# input4.net
KiCad netlist of a schematic drawn in Altium Designer
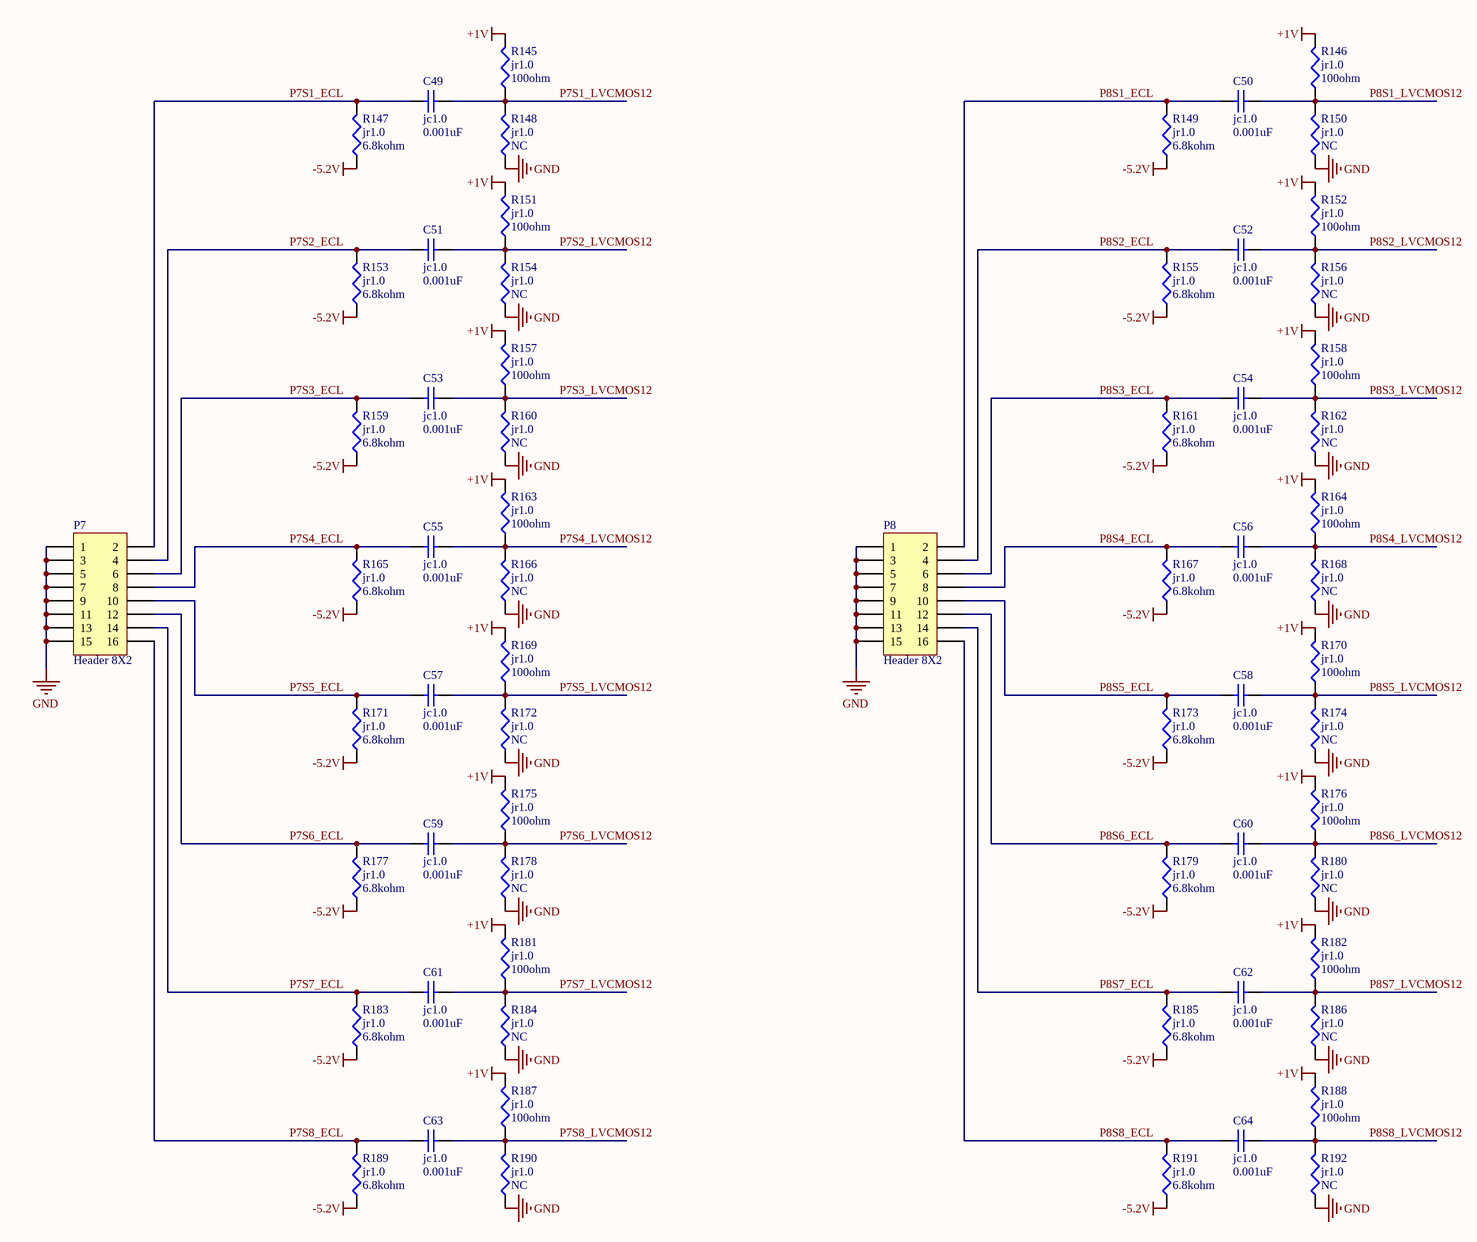
[diagram p0: input4.SchDoc]

(export (version "E")
  (design (tool "Eeschema 10.0.6"))
  (components
    (comp (ref "C49")
      (value "jc1.0")
      (footprint "0402")
      (description "Capacitor")
      (fields (field (name "ALTIUM_VALUE") "0.001uF") (field (name "PUBLISHER") "Altium Limited"))
      (libsource (lib "LIB01DXP2006SchLib") (part "Cap"))
    )
    (comp (ref "C50")
      (value "jc1.0")
      (footprint "0402")
      (description "Capacitor")
      (fields (field (name "ALTIUM_VALUE") "0.001uF") (field (name "PUBLISHER") "Altium Limited"))
      (libsource (lib "LIB01DXP2006SchLib") (part "Cap"))
    )
    (comp (ref "C51")
      (value "jc1.0")
      (footprint "0402")
      (description "Capacitor")
      (fields (field (name "ALTIUM_VALUE") "0.001uF") (field (name "PUBLISHER") "Altium Limited"))
      (libsource (lib "LIB01DXP2006SchLib") (part "Cap"))
    )
    (comp (ref "C52")
      (value "jc1.0")
      (footprint "0402")
      (description "Capacitor")
      (fields (field (name "ALTIUM_VALUE") "0.001uF") (field (name "PUBLISHER") "Altium Limited"))
      (libsource (lib "LIB01DXP2006SchLib") (part "Cap"))
    )
    (comp (ref "C53")
      (value "jc1.0")
      (footprint "0402")
      (description "Capacitor")
      (fields (field (name "ALTIUM_VALUE") "0.001uF") (field (name "PUBLISHER") "Altium Limited"))
      (libsource (lib "LIB01DXP2006SchLib") (part "Cap"))
    )
    (comp (ref "C54")
      (value "jc1.0")
      (footprint "0402")
      (description "Capacitor")
      (fields (field (name "ALTIUM_VALUE") "0.001uF") (field (name "PUBLISHER") "Altium Limited"))
      (libsource (lib "LIB01DXP2006SchLib") (part "Cap"))
    )
    (comp (ref "C55")
      (value "jc1.0")
      (footprint "0402")
      (description "Capacitor")
      (fields (field (name "ALTIUM_VALUE") "0.001uF") (field (name "PUBLISHER") "Altium Limited"))
      (libsource (lib "LIB01DXP2006SchLib") (part "Cap"))
    )
    (comp (ref "C56")
      (value "jc1.0")
      (footprint "0402")
      (description "Capacitor")
      (fields (field (name "ALTIUM_VALUE") "0.001uF") (field (name "PUBLISHER") "Altium Limited"))
      (libsource (lib "LIB01DXP2006SchLib") (part "Cap"))
    )
    (comp (ref "C57")
      (value "jc1.0")
      (footprint "0402")
      (description "Capacitor")
      (fields (field (name "ALTIUM_VALUE") "0.001uF") (field (name "PUBLISHER") "Altium Limited"))
      (libsource (lib "LIB01DXP2006SchLib") (part "Cap"))
    )
    (comp (ref "C58")
      (value "jc1.0")
      (footprint "0402")
      (description "Capacitor")
      (fields (field (name "ALTIUM_VALUE") "0.001uF") (field (name "PUBLISHER") "Altium Limited"))
      (libsource (lib "LIB01DXP2006SchLib") (part "Cap"))
    )
    (comp (ref "C59")
      (value "jc1.0")
      (footprint "0402")
      (description "Capacitor")
      (fields (field (name "ALTIUM_VALUE") "0.001uF") (field (name "PUBLISHER") "Altium Limited"))
      (libsource (lib "LIB01DXP2006SchLib") (part "Cap"))
    )
    (comp (ref "C60")
      (value "jc1.0")
      (footprint "0402")
      (description "Capacitor")
      (fields (field (name "ALTIUM_VALUE") "0.001uF") (field (name "PUBLISHER") "Altium Limited"))
      (libsource (lib "LIB01DXP2006SchLib") (part "Cap"))
    )
    (comp (ref "C61")
      (value "jc1.0")
      (footprint "0402")
      (description "Capacitor")
      (fields (field (name "ALTIUM_VALUE") "0.001uF") (field (name "PUBLISHER") "Altium Limited"))
      (libsource (lib "LIB01DXP2006SchLib") (part "Cap"))
    )
    (comp (ref "C62")
      (value "jc1.0")
      (footprint "0402")
      (description "Capacitor")
      (fields (field (name "ALTIUM_VALUE") "0.001uF") (field (name "PUBLISHER") "Altium Limited"))
      (libsource (lib "LIB01DXP2006SchLib") (part "Cap"))
    )
    (comp (ref "C63")
      (value "jc1.0")
      (footprint "0402")
      (description "Capacitor")
      (fields (field (name "ALTIUM_VALUE") "0.001uF") (field (name "PUBLISHER") "Altium Limited"))
      (libsource (lib "LIB01DXP2006SchLib") (part "Cap"))
    )
    (comp (ref "C64")
      (value "jc1.0")
      (footprint "0402")
      (description "Capacitor")
      (fields (field (name "ALTIUM_VALUE") "0.001uF") (field (name "PUBLISHER") "Altium Limited"))
      (libsource (lib "LIB01DXP2006SchLib") (part "Cap"))
    )
    (comp (ref "P7")
      (value "Header 8X2")
      (footprint "HDR2X8")
      (description "Header, 8-Pin, Dual row")
      (fields (field (name "PUBLISHER") "Altium Limited"))
      (libsource (lib "Miscellaneous Connectors") (part "Header 8X2"))
    )
    (comp (ref "P8")
      (value "Header 8X2")
      (footprint "HDR2X8")
      (description "Header, 8-Pin, Dual row")
      (fields (field (name "PUBLISHER") "Altium Limited"))
      (libsource (lib "Miscellaneous Connectors") (part "Header 8X2"))
    )
    (comp (ref "R145")
      (value "jr1.0")
      (footprint "0402")
      (description "Resistor")
      (fields (field (name "ALTIUM_VALUE") "100ohm") (field (name "PUBLISHER") "Altium Limited"))
      (libsource (lib "LIB01DXP2006SchLib") (part "Res"))
    )
    (comp (ref "R146")
      (value "jr1.0")
      (footprint "0402")
      (description "Resistor")
      (fields (field (name "ALTIUM_VALUE") "100ohm") (field (name "PUBLISHER") "Altium Limited"))
      (libsource (lib "LIB01DXP2006SchLib") (part "Res"))
    )
    (comp (ref "R147")
      (value "jr1.0")
      (footprint "0402")
      (description "Resistor")
      (fields (field (name "ALTIUM_VALUE") "6.8kohm") (field (name "PUBLISHER") "Altium Limited"))
      (libsource (lib "LIB01DXP2006SchLib") (part "Res"))
    )
    (comp (ref "R148")
      (value "jr1.0")
      (footprint "0402")
      (description "Resistor")
      (fields (field (name "ALTIUM_VALUE") "NC") (field (name "PUBLISHER") "Altium Limited"))
      (libsource (lib "LIB01DXP2006SchLib") (part "Res"))
    )
    (comp (ref "R149")
      (value "jr1.0")
      (footprint "0402")
      (description "Resistor")
      (fields (field (name "ALTIUM_VALUE") "6.8kohm") (field (name "PUBLISHER") "Altium Limited"))
      (libsource (lib "LIB01DXP2006SchLib") (part "Res"))
    )
    (comp (ref "R150")
      (value "jr1.0")
      (footprint "0402")
      (description "Resistor")
      (fields (field (name "ALTIUM_VALUE") "NC") (field (name "PUBLISHER") "Altium Limited"))
      (libsource (lib "LIB01DXP2006SchLib") (part "Res"))
    )
    (comp (ref "R151")
      (value "jr1.0")
      (footprint "0402")
      (description "Resistor")
      (fields (field (name "ALTIUM_VALUE") "100ohm") (field (name "PUBLISHER") "Altium Limited"))
      (libsource (lib "LIB01DXP2006SchLib") (part "Res"))
    )
    (comp (ref "R152")
      (value "jr1.0")
      (footprint "0402")
      (description "Resistor")
      (fields (field (name "ALTIUM_VALUE") "100ohm") (field (name "PUBLISHER") "Altium Limited"))
      (libsource (lib "LIB01DXP2006SchLib") (part "Res"))
    )
    (comp (ref "R153")
      (value "jr1.0")
      (footprint "0402")
      (description "Resistor")
      (fields (field (name "ALTIUM_VALUE") "6.8kohm") (field (name "PUBLISHER") "Altium Limited"))
      (libsource (lib "LIB01DXP2006SchLib") (part "Res"))
    )
    (comp (ref "R154")
      (value "jr1.0")
      (footprint "0402")
      (description "Resistor")
      (fields (field (name "ALTIUM_VALUE") "NC") (field (name "PUBLISHER") "Altium Limited"))
      (libsource (lib "LIB01DXP2006SchLib") (part "Res"))
    )
    (comp (ref "R155")
      (value "jr1.0")
      (footprint "0402")
      (description "Resistor")
      (fields (field (name "ALTIUM_VALUE") "6.8kohm") (field (name "PUBLISHER") "Altium Limited"))
      (libsource (lib "LIB01DXP2006SchLib") (part "Res"))
    )
    (comp (ref "R156")
      (value "jr1.0")
      (footprint "0402")
      (description "Resistor")
      (fields (field (name "ALTIUM_VALUE") "NC") (field (name "PUBLISHER") "Altium Limited"))
      (libsource (lib "LIB01DXP2006SchLib") (part "Res"))
    )
    (comp (ref "R157")
      (value "jr1.0")
      (footprint "0402")
      (description "Resistor")
      (fields (field (name "ALTIUM_VALUE") "100ohm") (field (name "PUBLISHER") "Altium Limited"))
      (libsource (lib "LIB01DXP2006SchLib") (part "Res"))
    )
    (comp (ref "R158")
      (value "jr1.0")
      (footprint "0402")
      (description "Resistor")
      (fields (field (name "ALTIUM_VALUE") "100ohm") (field (name "PUBLISHER") "Altium Limited"))
      (libsource (lib "LIB01DXP2006SchLib") (part "Res"))
    )
    (comp (ref "R159")
      (value "jr1.0")
      (footprint "0402")
      (description "Resistor")
      (fields (field (name "ALTIUM_VALUE") "6.8kohm") (field (name "PUBLISHER") "Altium Limited"))
      (libsource (lib "LIB01DXP2006SchLib") (part "Res"))
    )
    (comp (ref "R160")
      (value "jr1.0")
      (footprint "0402")
      (description "Resistor")
      (fields (field (name "ALTIUM_VALUE") "NC") (field (name "PUBLISHER") "Altium Limited"))
      (libsource (lib "LIB01DXP2006SchLib") (part "Res"))
    )
    (comp (ref "R161")
      (value "jr1.0")
      (footprint "0402")
      (description "Resistor")
      (fields (field (name "ALTIUM_VALUE") "6.8kohm") (field (name "PUBLISHER") "Altium Limited"))
      (libsource (lib "LIB01DXP2006SchLib") (part "Res"))
    )
    (comp (ref "R162")
      (value "jr1.0")
      (footprint "0402")
      (description "Resistor")
      (fields (field (name "ALTIUM_VALUE") "NC") (field (name "PUBLISHER") "Altium Limited"))
      (libsource (lib "LIB01DXP2006SchLib") (part "Res"))
    )
    (comp (ref "R163")
      (value "jr1.0")
      (footprint "0402")
      (description "Resistor")
      (fields (field (name "ALTIUM_VALUE") "100ohm") (field (name "PUBLISHER") "Altium Limited"))
      (libsource (lib "LIB01DXP2006SchLib") (part "Res"))
    )
    (comp (ref "R164")
      (value "jr1.0")
      (footprint "0402")
      (description "Resistor")
      (fields (field (name "ALTIUM_VALUE") "100ohm") (field (name "PUBLISHER") "Altium Limited"))
      (libsource (lib "LIB01DXP2006SchLib") (part "Res"))
    )
    (comp (ref "R165")
      (value "jr1.0")
      (footprint "0402")
      (description "Resistor")
      (fields (field (name "ALTIUM_VALUE") "6.8kohm") (field (name "PUBLISHER") "Altium Limited"))
      (libsource (lib "LIB01DXP2006SchLib") (part "Res"))
    )
    (comp (ref "R166")
      (value "jr1.0")
      (footprint "0402")
      (description "Resistor")
      (fields (field (name "ALTIUM_VALUE") "NC") (field (name "PUBLISHER") "Altium Limited"))
      (libsource (lib "LIB01DXP2006SchLib") (part "Res"))
    )
    (comp (ref "R167")
      (value "jr1.0")
      (footprint "0402")
      (description "Resistor")
      (fields (field (name "ALTIUM_VALUE") "6.8kohm") (field (name "PUBLISHER") "Altium Limited"))
      (libsource (lib "LIB01DXP2006SchLib") (part "Res"))
    )
    (comp (ref "R168")
      (value "jr1.0")
      (footprint "0402")
      (description "Resistor")
      (fields (field (name "ALTIUM_VALUE") "NC") (field (name "PUBLISHER") "Altium Limited"))
      (libsource (lib "LIB01DXP2006SchLib") (part "Res"))
    )
    (comp (ref "R169")
      (value "jr1.0")
      (footprint "0402")
      (description "Resistor")
      (fields (field (name "ALTIUM_VALUE") "100ohm") (field (name "PUBLISHER") "Altium Limited"))
      (libsource (lib "LIB01DXP2006SchLib") (part "Res"))
    )
    (comp (ref "R170")
      (value "jr1.0")
      (footprint "0402")
      (description "Resistor")
      (fields (field (name "ALTIUM_VALUE") "100ohm") (field (name "PUBLISHER") "Altium Limited"))
      (libsource (lib "LIB01DXP2006SchLib") (part "Res"))
    )
    (comp (ref "R171")
      (value "jr1.0")
      (footprint "0402")
      (description "Resistor")
      (fields (field (name "ALTIUM_VALUE") "6.8kohm") (field (name "PUBLISHER") "Altium Limited"))
      (libsource (lib "LIB01DXP2006SchLib") (part "Res"))
    )
    (comp (ref "R172")
      (value "jr1.0")
      (footprint "0402")
      (description "Resistor")
      (fields (field (name "ALTIUM_VALUE") "NC") (field (name "PUBLISHER") "Altium Limited"))
      (libsource (lib "LIB01DXP2006SchLib") (part "Res"))
    )
    (comp (ref "R173")
      (value "jr1.0")
      (footprint "0402")
      (description "Resistor")
      (fields (field (name "ALTIUM_VALUE") "6.8kohm") (field (name "PUBLISHER") "Altium Limited"))
      (libsource (lib "LIB01DXP2006SchLib") (part "Res"))
    )
    (comp (ref "R174")
      (value "jr1.0")
      (footprint "0402")
      (description "Resistor")
      (fields (field (name "ALTIUM_VALUE") "NC") (field (name "PUBLISHER") "Altium Limited"))
      (libsource (lib "LIB01DXP2006SchLib") (part "Res"))
    )
    (comp (ref "R175")
      (value "jr1.0")
      (footprint "0402")
      (description "Resistor")
      (fields (field (name "ALTIUM_VALUE") "100ohm") (field (name "PUBLISHER") "Altium Limited"))
      (libsource (lib "LIB01DXP2006SchLib") (part "Res"))
    )
    (comp (ref "R176")
      (value "jr1.0")
      (footprint "0402")
      (description "Resistor")
      (fields (field (name "ALTIUM_VALUE") "100ohm") (field (name "PUBLISHER") "Altium Limited"))
      (libsource (lib "LIB01DXP2006SchLib") (part "Res"))
    )
    (comp (ref "R177")
      (value "jr1.0")
      (footprint "0402")
      (description "Resistor")
      (fields (field (name "ALTIUM_VALUE") "6.8kohm") (field (name "PUBLISHER") "Altium Limited"))
      (libsource (lib "LIB01DXP2006SchLib") (part "Res"))
    )
    (comp (ref "R178")
      (value "jr1.0")
      (footprint "0402")
      (description "Resistor")
      (fields (field (name "ALTIUM_VALUE") "NC") (field (name "PUBLISHER") "Altium Limited"))
      (libsource (lib "LIB01DXP2006SchLib") (part "Res"))
    )
    (comp (ref "R179")
      (value "jr1.0")
      (footprint "0402")
      (description "Resistor")
      (fields (field (name "ALTIUM_VALUE") "6.8kohm") (field (name "PUBLISHER") "Altium Limited"))
      (libsource (lib "LIB01DXP2006SchLib") (part "Res"))
    )
    (comp (ref "R180")
      (value "jr1.0")
      (footprint "0402")
      (description "Resistor")
      (fields (field (name "ALTIUM_VALUE") "NC") (field (name "PUBLISHER") "Altium Limited"))
      (libsource (lib "LIB01DXP2006SchLib") (part "Res"))
    )
    (comp (ref "R181")
      (value "jr1.0")
      (footprint "0402")
      (description "Resistor")
      (fields (field (name "ALTIUM_VALUE") "100ohm") (field (name "PUBLISHER") "Altium Limited"))
      (libsource (lib "LIB01DXP2006SchLib") (part "Res"))
    )
    (comp (ref "R182")
      (value "jr1.0")
      (footprint "0402")
      (description "Resistor")
      (fields (field (name "ALTIUM_VALUE") "100ohm") (field (name "PUBLISHER") "Altium Limited"))
      (libsource (lib "LIB01DXP2006SchLib") (part "Res"))
    )
    (comp (ref "R183")
      (value "jr1.0")
      (footprint "0402")
      (description "Resistor")
      (fields (field (name "ALTIUM_VALUE") "6.8kohm") (field (name "PUBLISHER") "Altium Limited"))
      (libsource (lib "LIB01DXP2006SchLib") (part "Res"))
    )
    (comp (ref "R184")
      (value "jr1.0")
      (footprint "0402")
      (description "Resistor")
      (fields (field (name "ALTIUM_VALUE") "NC") (field (name "PUBLISHER") "Altium Limited"))
      (libsource (lib "LIB01DXP2006SchLib") (part "Res"))
    )
    (comp (ref "R185")
      (value "jr1.0")
      (footprint "0402")
      (description "Resistor")
      (fields (field (name "ALTIUM_VALUE") "6.8kohm") (field (name "PUBLISHER") "Altium Limited"))
      (libsource (lib "LIB01DXP2006SchLib") (part "Res"))
    )
    (comp (ref "R186")
      (value "jr1.0")
      (footprint "0402")
      (description "Resistor")
      (fields (field (name "ALTIUM_VALUE") "NC") (field (name "PUBLISHER") "Altium Limited"))
      (libsource (lib "LIB01DXP2006SchLib") (part "Res"))
    )
    (comp (ref "R187")
      (value "jr1.0")
      (footprint "0402")
      (description "Resistor")
      (fields (field (name "ALTIUM_VALUE") "100ohm") (field (name "PUBLISHER") "Altium Limited"))
      (libsource (lib "LIB01DXP2006SchLib") (part "Res"))
    )
    (comp (ref "R188")
      (value "jr1.0")
      (footprint "0402")
      (description "Resistor")
      (fields (field (name "ALTIUM_VALUE") "100ohm") (field (name "PUBLISHER") "Altium Limited"))
      (libsource (lib "LIB01DXP2006SchLib") (part "Res"))
    )
    (comp (ref "R189")
      (value "jr1.0")
      (footprint "0402")
      (description "Resistor")
      (fields (field (name "ALTIUM_VALUE") "6.8kohm") (field (name "PUBLISHER") "Altium Limited"))
      (libsource (lib "LIB01DXP2006SchLib") (part "Res"))
    )
    (comp (ref "R190")
      (value "jr1.0")
      (footprint "0402")
      (description "Resistor")
      (fields (field (name "ALTIUM_VALUE") "NC") (field (name "PUBLISHER") "Altium Limited"))
      (libsource (lib "LIB01DXP2006SchLib") (part "Res"))
    )
    (comp (ref "R191")
      (value "jr1.0")
      (footprint "0402")
      (description "Resistor")
      (fields (field (name "ALTIUM_VALUE") "6.8kohm") (field (name "PUBLISHER") "Altium Limited"))
      (libsource (lib "LIB01DXP2006SchLib") (part "Res"))
    )
    (comp (ref "R192")
      (value "jr1.0")
      (footprint "0402")
      (description "Resistor")
      (fields (field (name "ALTIUM_VALUE") "NC") (field (name "PUBLISHER") "Altium Limited"))
      (libsource (lib "LIB01DXP2006SchLib") (part "Res"))
    )
  )
  (nets
    (net (code "1") (name "+1V") (class "Default")
      (node (ref "R145") (pin "2") (pinfunction "2_2") (pintype "passive"))
      (node (ref "R146") (pin "2") (pinfunction "2_2") (pintype "passive"))
      (node (ref "R151") (pin "2") (pinfunction "2_2") (pintype "passive"))
      (node (ref "R152") (pin "2") (pinfunction "2_2") (pintype "passive"))
      (node (ref "R157") (pin "2") (pinfunction "2_2") (pintype "passive"))
      (node (ref "R158") (pin "2") (pinfunction "2_2") (pintype "passive"))
      (node (ref "R163") (pin "2") (pinfunction "2_2") (pintype "passive"))
      (node (ref "R164") (pin "2") (pinfunction "2_2") (pintype "passive"))
      (node (ref "R169") (pin "2") (pinfunction "2_2") (pintype "passive"))
      (node (ref "R170") (pin "2") (pinfunction "2_2") (pintype "passive"))
      (node (ref "R175") (pin "2") (pinfunction "2_2") (pintype "passive"))
      (node (ref "R176") (pin "2") (pinfunction "2_2") (pintype "passive"))
      (node (ref "R181") (pin "2") (pinfunction "2_2") (pintype "passive"))
      (node (ref "R182") (pin "2") (pinfunction "2_2") (pintype "passive"))
      (node (ref "R187") (pin "2") (pinfunction "2_2") (pintype "passive"))
      (node (ref "R188") (pin "2") (pinfunction "2_2") (pintype "passive"))
    )
    (net (code "2") (name "-5.2V") (class "Default")
      (node (ref "R147") (pin "1") (pinfunction "1_1") (pintype "passive"))
      (node (ref "R149") (pin "1") (pinfunction "1_1") (pintype "passive"))
      (node (ref "R153") (pin "1") (pinfunction "1_1") (pintype "passive"))
      (node (ref "R155") (pin "1") (pinfunction "1_1") (pintype "passive"))
      (node (ref "R159") (pin "1") (pinfunction "1_1") (pintype "passive"))
      (node (ref "R161") (pin "1") (pinfunction "1_1") (pintype "passive"))
      (node (ref "R165") (pin "1") (pinfunction "1_1") (pintype "passive"))
      (node (ref "R167") (pin "1") (pinfunction "1_1") (pintype "passive"))
      (node (ref "R171") (pin "1") (pinfunction "1_1") (pintype "passive"))
      (node (ref "R173") (pin "1") (pinfunction "1_1") (pintype "passive"))
      (node (ref "R177") (pin "1") (pinfunction "1_1") (pintype "passive"))
      (node (ref "R179") (pin "1") (pinfunction "1_1") (pintype "passive"))
      (node (ref "R183") (pin "1") (pinfunction "1_1") (pintype "passive"))
      (node (ref "R185") (pin "1") (pinfunction "1_1") (pintype "passive"))
      (node (ref "R189") (pin "1") (pinfunction "1_1") (pintype "passive"))
      (node (ref "R191") (pin "1") (pinfunction "1_1") (pintype "passive"))
    )
    (net (code "3") (name "/P7S1_ECL") (class "Default")
      (node (ref "C49") (pin "1") (pinfunction "1_1") (pintype "passive"))
      (node (ref "P7") (pin "2") (pinfunction "2_2") (pintype "passive"))
      (node (ref "R147") (pin "2") (pinfunction "2_2") (pintype "passive"))
    )
    (net (code "4") (name "/P7S1_LVCMOS12") (class "Default")
      (node (ref "C49") (pin "2") (pinfunction "2_2") (pintype "passive"))
      (node (ref "R145") (pin "1") (pinfunction "1_1") (pintype "passive"))
      (node (ref "R148") (pin "2") (pinfunction "2_2") (pintype "passive"))
    )
    (net (code "5") (name "/P7S2_ECL") (class "Default")
      (node (ref "C51") (pin "1") (pinfunction "1_1") (pintype "passive"))
      (node (ref "P7") (pin "4") (pinfunction "4_4") (pintype "passive"))
      (node (ref "R153") (pin "2") (pinfunction "2_2") (pintype "passive"))
    )
    (net (code "6") (name "/P7S2_LVCMOS12") (class "Default")
      (node (ref "C51") (pin "2") (pinfunction "2_2") (pintype "passive"))
      (node (ref "R151") (pin "1") (pinfunction "1_1") (pintype "passive"))
      (node (ref "R154") (pin "2") (pinfunction "2_2") (pintype "passive"))
    )
    (net (code "7") (name "/P7S3_ECL") (class "Default")
      (node (ref "C53") (pin "1") (pinfunction "1_1") (pintype "passive"))
      (node (ref "P7") (pin "6") (pinfunction "6_6") (pintype "passive"))
      (node (ref "R159") (pin "2") (pinfunction "2_2") (pintype "passive"))
    )
    (net (code "8") (name "/P7S3_LVCMOS12") (class "Default")
      (node (ref "C53") (pin "2") (pinfunction "2_2") (pintype "passive"))
      (node (ref "R157") (pin "1") (pinfunction "1_1") (pintype "passive"))
      (node (ref "R160") (pin "2") (pinfunction "2_2") (pintype "passive"))
    )
    (net (code "9") (name "/P7S4_ECL") (class "Default")
      (node (ref "C55") (pin "1") (pinfunction "1_1") (pintype "passive"))
      (node (ref "P7") (pin "8") (pinfunction "8_8") (pintype "passive"))
      (node (ref "R165") (pin "2") (pinfunction "2_2") (pintype "passive"))
    )
    (net (code "10") (name "/P7S4_LVCMOS12") (class "Default")
      (node (ref "C55") (pin "2") (pinfunction "2_2") (pintype "passive"))
      (node (ref "R163") (pin "1") (pinfunction "1_1") (pintype "passive"))
      (node (ref "R166") (pin "2") (pinfunction "2_2") (pintype "passive"))
    )
    (net (code "11") (name "/P7S5_ECL") (class "Default")
      (node (ref "C57") (pin "1") (pinfunction "1_1") (pintype "passive"))
      (node (ref "P7") (pin "10") (pinfunction "10_10") (pintype "passive"))
      (node (ref "R171") (pin "2") (pinfunction "2_2") (pintype "passive"))
    )
    (net (code "12") (name "/P7S5_LVCMOS12") (class "Default")
      (node (ref "C57") (pin "2") (pinfunction "2_2") (pintype "passive"))
      (node (ref "R169") (pin "1") (pinfunction "1_1") (pintype "passive"))
      (node (ref "R172") (pin "2") (pinfunction "2_2") (pintype "passive"))
    )
    (net (code "13") (name "/P7S6_ECL") (class "Default")
      (node (ref "C59") (pin "1") (pinfunction "1_1") (pintype "passive"))
      (node (ref "P7") (pin "12") (pinfunction "12_12") (pintype "passive"))
      (node (ref "R177") (pin "2") (pinfunction "2_2") (pintype "passive"))
    )
    (net (code "14") (name "/P7S6_LVCMOS12") (class "Default")
      (node (ref "C59") (pin "2") (pinfunction "2_2") (pintype "passive"))
      (node (ref "R175") (pin "1") (pinfunction "1_1") (pintype "passive"))
      (node (ref "R178") (pin "2") (pinfunction "2_2") (pintype "passive"))
    )
    (net (code "15") (name "/P7S7_ECL") (class "Default")
      (node (ref "C61") (pin "1") (pinfunction "1_1") (pintype "passive"))
      (node (ref "P7") (pin "14") (pinfunction "14_14") (pintype "passive"))
      (node (ref "R183") (pin "2") (pinfunction "2_2") (pintype "passive"))
    )
    (net (code "16") (name "/P7S7_LVCMOS12") (class "Default")
      (node (ref "C61") (pin "2") (pinfunction "2_2") (pintype "passive"))
      (node (ref "R181") (pin "1") (pinfunction "1_1") (pintype "passive"))
      (node (ref "R184") (pin "2") (pinfunction "2_2") (pintype "passive"))
    )
    (net (code "17") (name "/P7S8_ECL") (class "Default")
      (node (ref "C63") (pin "1") (pinfunction "1_1") (pintype "passive"))
      (node (ref "P7") (pin "16") (pinfunction "16_16") (pintype "passive"))
      (node (ref "R189") (pin "2") (pinfunction "2_2") (pintype "passive"))
    )
    (net (code "18") (name "/P7S8_LVCMOS12") (class "Default")
      (node (ref "C63") (pin "2") (pinfunction "2_2") (pintype "passive"))
      (node (ref "R187") (pin "1") (pinfunction "1_1") (pintype "passive"))
      (node (ref "R190") (pin "2") (pinfunction "2_2") (pintype "passive"))
    )
    (net (code "19") (name "/P8S1_ECL") (class "Default")
      (node (ref "C50") (pin "1") (pinfunction "1_1") (pintype "passive"))
      (node (ref "P8") (pin "2") (pinfunction "2_2") (pintype "passive"))
      (node (ref "R149") (pin "2") (pinfunction "2_2") (pintype "passive"))
    )
    (net (code "20") (name "/P8S1_LVCMOS12") (class "Default")
      (node (ref "C50") (pin "2") (pinfunction "2_2") (pintype "passive"))
      (node (ref "R146") (pin "1") (pinfunction "1_1") (pintype "passive"))
      (node (ref "R150") (pin "2") (pinfunction "2_2") (pintype "passive"))
    )
    (net (code "21") (name "/P8S2_ECL") (class "Default")
      (node (ref "C52") (pin "1") (pinfunction "1_1") (pintype "passive"))
      (node (ref "P8") (pin "4") (pinfunction "4_4") (pintype "passive"))
      (node (ref "R155") (pin "2") (pinfunction "2_2") (pintype "passive"))
    )
    (net (code "22") (name "/P8S2_LVCMOS12") (class "Default")
      (node (ref "C52") (pin "2") (pinfunction "2_2") (pintype "passive"))
      (node (ref "R152") (pin "1") (pinfunction "1_1") (pintype "passive"))
      (node (ref "R156") (pin "2") (pinfunction "2_2") (pintype "passive"))
    )
    (net (code "23") (name "/P8S3_ECL") (class "Default")
      (node (ref "C54") (pin "1") (pinfunction "1_1") (pintype "passive"))
      (node (ref "P8") (pin "6") (pinfunction "6_6") (pintype "passive"))
      (node (ref "R161") (pin "2") (pinfunction "2_2") (pintype "passive"))
    )
    (net (code "24") (name "/P8S3_LVCMOS12") (class "Default")
      (node (ref "C54") (pin "2") (pinfunction "2_2") (pintype "passive"))
      (node (ref "R158") (pin "1") (pinfunction "1_1") (pintype "passive"))
      (node (ref "R162") (pin "2") (pinfunction "2_2") (pintype "passive"))
    )
    (net (code "25") (name "/P8S4_ECL") (class "Default")
      (node (ref "C56") (pin "1") (pinfunction "1_1") (pintype "passive"))
      (node (ref "P8") (pin "8") (pinfunction "8_8") (pintype "passive"))
      (node (ref "R167") (pin "2") (pinfunction "2_2") (pintype "passive"))
    )
    (net (code "26") (name "/P8S4_LVCMOS12") (class "Default")
      (node (ref "C56") (pin "2") (pinfunction "2_2") (pintype "passive"))
      (node (ref "R164") (pin "1") (pinfunction "1_1") (pintype "passive"))
      (node (ref "R168") (pin "2") (pinfunction "2_2") (pintype "passive"))
    )
    (net (code "27") (name "/P8S5_ECL") (class "Default")
      (node (ref "C58") (pin "1") (pinfunction "1_1") (pintype "passive"))
      (node (ref "P8") (pin "10") (pinfunction "10_10") (pintype "passive"))
      (node (ref "R173") (pin "2") (pinfunction "2_2") (pintype "passive"))
    )
    (net (code "28") (name "/P8S5_LVCMOS12") (class "Default")
      (node (ref "C58") (pin "2") (pinfunction "2_2") (pintype "passive"))
      (node (ref "R170") (pin "1") (pinfunction "1_1") (pintype "passive"))
      (node (ref "R174") (pin "2") (pinfunction "2_2") (pintype "passive"))
    )
    (net (code "29") (name "/P8S6_ECL") (class "Default")
      (node (ref "C60") (pin "1") (pinfunction "1_1") (pintype "passive"))
      (node (ref "P8") (pin "12") (pinfunction "12_12") (pintype "passive"))
      (node (ref "R179") (pin "2") (pinfunction "2_2") (pintype "passive"))
    )
    (net (code "30") (name "/P8S6_LVCMOS12") (class "Default")
      (node (ref "C60") (pin "2") (pinfunction "2_2") (pintype "passive"))
      (node (ref "R176") (pin "1") (pinfunction "1_1") (pintype "passive"))
      (node (ref "R180") (pin "2") (pinfunction "2_2") (pintype "passive"))
    )
    (net (code "31") (name "/P8S7_ECL") (class "Default")
      (node (ref "C62") (pin "1") (pinfunction "1_1") (pintype "passive"))
      (node (ref "P8") (pin "14") (pinfunction "14_14") (pintype "passive"))
      (node (ref "R185") (pin "2") (pinfunction "2_2") (pintype "passive"))
    )
    (net (code "32") (name "/P8S7_LVCMOS12") (class "Default")
      (node (ref "C62") (pin "2") (pinfunction "2_2") (pintype "passive"))
      (node (ref "R182") (pin "1") (pinfunction "1_1") (pintype "passive"))
      (node (ref "R186") (pin "2") (pinfunction "2_2") (pintype "passive"))
    )
    (net (code "33") (name "/P8S8_ECL") (class "Default")
      (node (ref "C64") (pin "1") (pinfunction "1_1") (pintype "passive"))
      (node (ref "P8") (pin "16") (pinfunction "16_16") (pintype "passive"))
      (node (ref "R191") (pin "2") (pinfunction "2_2") (pintype "passive"))
    )
    (net (code "34") (name "/P8S8_LVCMOS12") (class "Default")
      (node (ref "C64") (pin "2") (pinfunction "2_2") (pintype "passive"))
      (node (ref "R188") (pin "1") (pinfunction "1_1") (pintype "passive"))
      (node (ref "R192") (pin "2") (pinfunction "2_2") (pintype "passive"))
    )
    (net (code "35") (name "GND") (class "Default")
      (node (ref "P7") (pin "1") (pinfunction "1_1") (pintype "passive"))
      (node (ref "P7") (pin "11") (pinfunction "11_11") (pintype "passive"))
      (node (ref "P7") (pin "13") (pinfunction "13_13") (pintype "passive"))
      (node (ref "P7") (pin "15") (pinfunction "15_15") (pintype "passive"))
      (node (ref "P7") (pin "3") (pinfunction "3_3") (pintype "passive"))
      (node (ref "P7") (pin "5") (pinfunction "5_5") (pintype "passive"))
      (node (ref "P7") (pin "7") (pinfunction "7_7") (pintype "passive"))
      (node (ref "P7") (pin "9") (pinfunction "9_9") (pintype "passive"))
      (node (ref "P8") (pin "1") (pinfunction "1_1") (pintype "passive"))
      (node (ref "P8") (pin "11") (pinfunction "11_11") (pintype "passive"))
      (node (ref "P8") (pin "13") (pinfunction "13_13") (pintype "passive"))
      (node (ref "P8") (pin "15") (pinfunction "15_15") (pintype "passive"))
      (node (ref "P8") (pin "3") (pinfunction "3_3") (pintype "passive"))
      (node (ref "P8") (pin "5") (pinfunction "5_5") (pintype "passive"))
      (node (ref "P8") (pin "7") (pinfunction "7_7") (pintype "passive"))
      (node (ref "P8") (pin "9") (pinfunction "9_9") (pintype "passive"))
      (node (ref "R148") (pin "1") (pinfunction "1_1") (pintype "passive"))
      (node (ref "R150") (pin "1") (pinfunction "1_1") (pintype "passive"))
      (node (ref "R154") (pin "1") (pinfunction "1_1") (pintype "passive"))
      (node (ref "R156") (pin "1") (pinfunction "1_1") (pintype "passive"))
      (node (ref "R160") (pin "1") (pinfunction "1_1") (pintype "passive"))
      (node (ref "R162") (pin "1") (pinfunction "1_1") (pintype "passive"))
      (node (ref "R166") (pin "1") (pinfunction "1_1") (pintype "passive"))
      (node (ref "R168") (pin "1") (pinfunction "1_1") (pintype "passive"))
      (node (ref "R172") (pin "1") (pinfunction "1_1") (pintype "passive"))
      (node (ref "R174") (pin "1") (pinfunction "1_1") (pintype "passive"))
      (node (ref "R178") (pin "1") (pinfunction "1_1") (pintype "passive"))
      (node (ref "R180") (pin "1") (pinfunction "1_1") (pintype "passive"))
      (node (ref "R184") (pin "1") (pinfunction "1_1") (pintype "passive"))
      (node (ref "R186") (pin "1") (pinfunction "1_1") (pintype "passive"))
      (node (ref "R190") (pin "1") (pinfunction "1_1") (pintype "passive"))
      (node (ref "R192") (pin "1") (pinfunction "1_1") (pintype "passive"))
    )
  )
)
